# Schematic_khodaparast.net
KiCad netlist of a schematic drawn in Altium Designer
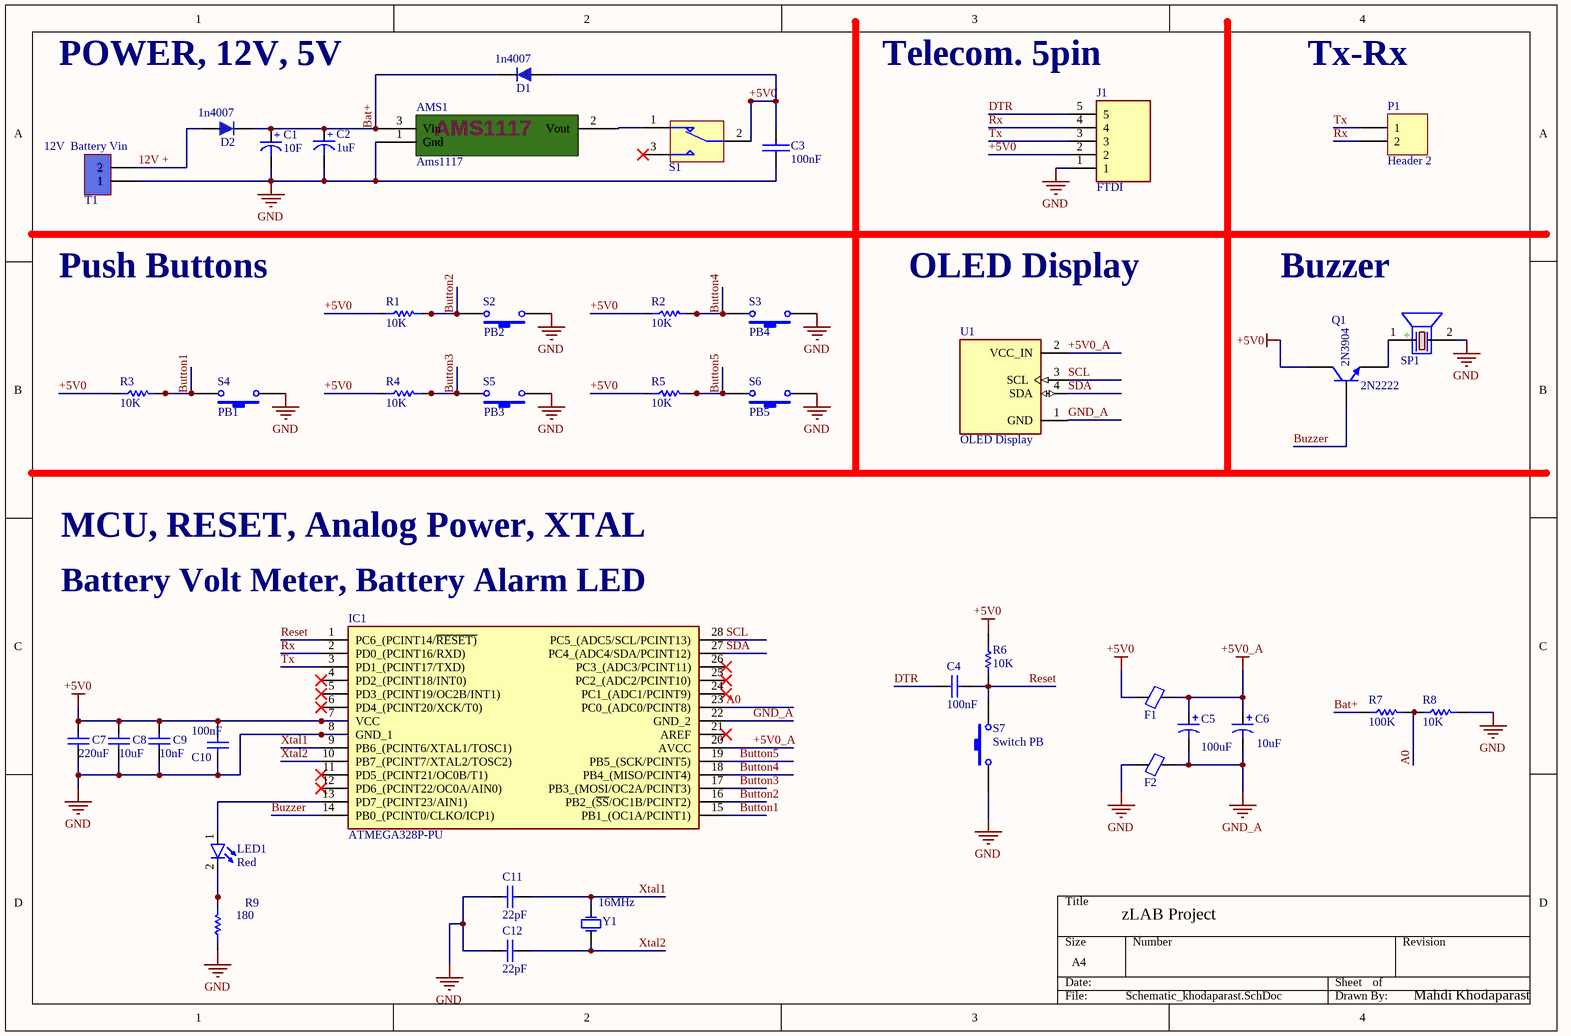
[diagram p0: Schematic_khodaparast.SchDoc]

(export (version "E")
  (design (tool "Eeschema 10.0.6"))
  (components
    (comp (ref "AMS1")
      (value "Ams1117")
      (footprint "Ams1117-3v3")
      (libsource (lib "AMS1117") (part "Ams1117"))
    )
    (comp (ref "C1")
      (value "10F")
      (footprint "Cap1206_(3216X18L)Size A")
      (description "Polar Capacitor")
      (fields (field (name "VOLTAGE") "16V") (field (name "DESIGNER") "Saeid Jorablo"))
      (libsource (lib "full (2)") (part "Cap-Polar"))
    )
    (comp (ref "C2")
      (value "1uF")
      (footprint "Cap1206_(3216X18L)Size A")
      (description "Polar Capacitor")
      (fields (field (name "VOLTAGE") "16V") (field (name "DESIGNER") "Saeid Jorablo"))
      (libsource (lib "full (2)") (part "Cap-Polar"))
    )
    (comp (ref "C3")
      (value "100nF")
      (footprint "CAP805")
      (description "Bipolar Capacitor")
      (fields (field (name "VOLTAGE") "100V") (field (name "DESIGNER") "Saeid Jorablo"))
      (libsource (lib "full (2)") (part "Cap-Bipolar"))
    )
    (comp (ref "C4")
      (value "100nF")
      (footprint "CAP805")
      (description "CAP 0805")
      (fields (field (name "DESIGNER") "Abbas Basereh"))
      (libsource (lib "Altium") (part "CAP SMD 0805"))
    )
    (comp (ref "C5")
      (value "100uF")
      (footprint "Cap1206_(3216X18L)Size A")
      (description "Polarized Capacitor (Radial)")
      (fields (field (name "Comment") "Cap Pol1") (field (name "PUBLISHER") "Altium Limited"))
      (libsource (lib "Miscellaneous Devices") (part "Cap Pol1"))
    )
    (comp (ref "C6")
      (value "10uF")
      (footprint "Cap1206_(3216X18L)Size A")
      (description "Polarized Capacitor (Radial)")
      (fields (field (name "Comment") "Cap Pol1") (field (name "PUBLISHER") "Altium Limited"))
      (libsource (lib "Miscellaneous Devices") (part "Cap Pol1"))
    )
    (comp (ref "C7")
      (value "220uF")
      (footprint "CAP805")
      (description "Capacitor")
      (fields (field (name "Comment") "Cap") (field (name "PUBLISHER") "Altium Limited"))
      (libsource (lib "Miscellaneous Devices") (part "Cap"))
    )
    (comp (ref "C8")
      (value "10uF")
      (footprint "CAP805")
      (description "Capacitor")
      (fields (field (name "Comment") "Cap") (field (name "PUBLISHER") "Altium Limited"))
      (libsource (lib "Miscellaneous Devices") (part "Cap"))
    )
    (comp (ref "C9")
      (value "10nF")
      (footprint "CAP805")
      (description "Capacitor")
      (fields (field (name "Comment") "Cap") (field (name "PUBLISHER") "Altium Limited"))
      (libsource (lib "Miscellaneous Devices") (part "Cap"))
    )
    (comp (ref "C10")
      (value "100nF")
      (footprint "CAP805")
      (description "CAP 0805")
      (fields (field (name "DESIGNER") "Abbas Basereh"))
      (libsource (lib "Altium") (part "CAP SMD 0805"))
    )
    (comp (ref "C11")
      (value "22pF")
      (footprint "CAP805")
      (description "CAP 0805")
      (fields (field (name "DESIGNER") "Abbas Basereh"))
      (libsource (lib "Altium") (part "CAP SMD 0805"))
    )
    (comp (ref "C12")
      (value "22pF")
      (footprint "CAP805")
      (description "CAP 0805")
      (fields (field (name "DESIGNER") "Abbas Basereh"))
      (libsource (lib "Altium") (part "CAP SMD 0805"))
    )
    (comp (ref "D1")
      (value "1n4007")
      (footprint "DIOM4629X24N")
      (description "Standard Rectifiers")
      (fields (field (name "MANUFACTURER") "DC COMPONENTS") (field (name "DESIGNER") "Abbas Basereh"))
      (libsource (lib "Altium") (part "1n4007 SMD M7"))
    )
    (comp (ref "D2")
      (value "1n4007")
      (footprint "DIOM4629X24N")
      (description "Standard Rectifiers")
      (fields (field (name "MANUFACTURER") "DC COMPONENTS") (field (name "DESIGNER") "Abbas Basereh"))
      (libsource (lib "Altium") (part "1n4007 SMD M7"))
    )
    (comp (ref "F1")
      (value "Ferrite Bead SMD")
      (footprint "FB0805")
      (fields (field (name "DESIGNER") "Ali Hafizi"))
      (libsource (lib "Altium") (part "Ferrite Bead SMD Package"))
    )
    (comp (ref "F2")
      (value "Ferrite Bead SMD")
      (footprint "FB0805")
      (fields (field (name "DESIGNER") "Ali Hafizi"))
      (libsource (lib "Altium") (part "Ferrite Bead SMD Package"))
    )
    (comp (ref "IC1")
      (value "ATMEGA328P-PU")
      (footprint "27_DIP_7.62mm")
      (description "Integrated Circuit")
      (fields (field (name "MOUSER PART NUMBER") "556-ATMEGA328P-PU"))
      (libsource (lib "SamacSys") (part "ATMEGA328P-PU"))
    )
    (comp (ref "J1")
      (value "FTDI")
      (footprint "HDR1X5")
      (description "Connector")
      (fields
        (field (name "MANUFACTURER_PART_NUMBER") "171813-0005")
        (field (name "MOUSER PART NUMBER") "538-171813-0005")
      )
      (libsource (lib "*") (part "171813-0005"))
    )
    (comp (ref "LED1")
      (value "Red")
      (footprint "LED-RED")
      (description "LED")
      (fields (field (name "COLOR") "Red") (field (name "DESIGNER") "Saeid Jorablo"))
      (libsource (lib "full (2)") (part "LED"))
    )
    (comp (ref "P1")
      (value "Header 2")
      (footprint "HDR1X2")
      (description "Header, 2-Pin")
      (fields (field (name "PUBLISHER") "Altium Limited"))
      (libsource (lib "Altium") (part "Header 2"))
    )
    (comp (ref "Q1")
      (value "2N2222")
      (footprint "2N3904")
      (description "NPN Transistor")
      (libsource (lib "Altium") (part "2N3904"))
    )
    (comp (ref "R1")
      (value "10K")
      (footprint "RES 0805 (2012X06L)")
      (description "Resistor")
      (fields (field (name "TOLERANCE") "5%") (field (name "POWER") "1/8 W"))
      (libsource (lib "full (2)") (part "Resistor"))
    )
    (comp (ref "R2")
      (value "10K")
      (footprint "RES 0805 (2012X06L)")
      (description "Resistor")
      (fields (field (name "TOLERANCE") "5%") (field (name "POWER") "1/8 W"))
      (libsource (lib "full (2)") (part "Resistor"))
    )
    (comp (ref "R3")
      (value "10K")
      (footprint "RES 0805 (2012X06L)")
      (description "Resistor")
      (fields (field (name "TOLERANCE") "5%") (field (name "POWER") "1/8 W"))
      (libsource (lib "full (2)") (part "Resistor"))
    )
    (comp (ref "R4")
      (value "10K")
      (footprint "RES 0805 (2012X06L)")
      (description "Resistor")
      (fields (field (name "TOLERANCE") "5%") (field (name "POWER") "1/8 W"))
      (libsource (lib "full (2)") (part "Resistor"))
    )
    (comp (ref "R5")
      (value "10K")
      (footprint "RES 0805 (2012X06L)")
      (description "Resistor")
      (fields (field (name "TOLERANCE") "5%") (field (name "POWER") "1/8 W"))
      (libsource (lib "full (2)") (part "Resistor"))
    )
    (comp (ref "R6")
      (value "10K")
      (footprint "RES 0805 (2012X06L)")
      (description "Resistor")
      (fields (field (name "Comment") "Res1") (field (name "PUBLISHER") "Altium Limited"))
      (libsource (lib "Miscellaneous Devices") (part "Res1"))
    )
    (comp (ref "R7")
      (value "100K")
      (footprint "RES 0805 (2012X06L)")
      (description "Resistor")
      (fields (field (name "TOLERANCE") "5%") (field (name "POWER") "1/8 W"))
      (libsource (lib "full (2)") (part "Resistor"))
    )
    (comp (ref "R8")
      (value "10K")
      (footprint "RES 0805 (2012X06L)")
      (description "Resistor")
      (fields (field (name "TOLERANCE") "5%") (field (name "POWER") "1/8 W"))
      (libsource (lib "full (2)") (part "Resistor"))
    )
    (comp (ref "R9")
      (value "180")
      (footprint "RES 0805 (2012X06L)")
      (description "Resistor")
      (fields (field (name "TOLERANCE") "5%") (field (name "POWER") "1/8 W"))
      (libsource (lib "full (2)") (part "Resistor"))
    )
    (comp (ref "S1")
      (value "Switch SPDT_Subminiator")
      (footprint "SPDT Subminiator")
      (description "Subminiator SPDT Switch")
      (libsource (lib "full (2)") (part "Switch SPDT_Subminiator"))
    )
    (comp (ref "S2")
      (value "PB2")
      (footprint "SW-PB")
      (description "Push Button Switch")
      (libsource (lib "full (2)") (part "Switch PB"))
    )
    (comp (ref "S3")
      (value "PB4")
      (footprint "SW-PB")
      (description "Push Button Switch")
      (libsource (lib "full (2)") (part "Switch PB"))
    )
    (comp (ref "S4")
      (value "PB1")
      (footprint "SW-PB")
      (description "Push Button Switch")
      (libsource (lib "full (2)") (part "Switch PB"))
    )
    (comp (ref "S5")
      (value "PB3")
      (footprint "SW-PB")
      (description "Push Button Switch")
      (libsource (lib "full (2)") (part "Switch PB"))
    )
    (comp (ref "S6")
      (value "PB5")
      (footprint "SW-PB")
      (description "Push Button Switch")
      (libsource (lib "full (2)") (part "Switch PB"))
    )
    (comp (ref "S7")
      (value "Switch PB")
      (footprint "SW-PB")
      (description "Push Button Switch")
      (libsource (lib "full (2)") (part "Switch PB"))
    )
    (comp (ref "SP1")
      (value "~")
      (footprint "BUZZER 7.62mm DC")
      (description "PIEZO BUZZER ACTIVE")
      (fields (field (name "DESIGNER") "Abbas Basereh") (field (name "PUBLISHER") "Abbas Basereh"))
      (libsource (lib "Altium") (part "PIEZO BUZZER"))
    )
    (comp (ref "T1")
      (value "12V  Battery Vin")
      (footprint "KF301 2PIN")
      (description "Terminal 2 Pin 250VAC 16A")
      (fields (field (name "DESIGNER") "Abbas Basereh"))
      (libsource (lib "Altium") (part "KF301-2Pin_Terminal"))
    )
    (comp (ref "U1")
      (value "OLED Display")
      (footprint "MODULE_DM-OLED096-636")
      (description "0.96â€ 128 X 64 MONOCHROME GRAPHIC OLED DISPLAY MODULE - I2C")
      (fields (field (name "MF") "Display Module") (field (name "MP") "DM-OLED096-636"))
      (libsource (lib "DM-OLED096-636") (part "DM-OLED096-636"))
    )
    (comp (ref "Y1")
      (value "16MHz")
      (footprint "XTAL 16MHZ")
      (description "XTAL Crystal")
      (fields (field (name "DESIGNER") "ABBAS BASEREH"))
      (libsource (lib "Altium") (part "XTAL"))
    )
  )
  (nets
    (net (code "1") (name "+5V0") (class "Default")
      (node (ref "C10") (pin "1") (pinfunction "1_1") (pintype "passive"))
      (node (ref "C3") (pin "1") (pinfunction "+_1") (pintype "passive"))
      (node (ref "C7") (pin "2") (pinfunction "2_2") (pintype "passive"))
      (node (ref "C8") (pin "2") (pinfunction "2_2") (pintype "passive"))
      (node (ref "C9") (pin "2") (pinfunction "2_2") (pintype "passive"))
      (node (ref "D1") (pin "1") (pintype "passive"))
      (node (ref "F1") (pin "1") (pinfunction "1_1") (pintype "passive"))
      (node (ref "IC1") (pin "7") (pinfunction "VCC_7") (pintype "passive"))
      (node (ref "J1") (pin "2") (pinfunction "2_2") (pintype "passive"))
      (node (ref "Q1") (pin "3") (pinfunction "C_3") (pintype "passive"))
      (node (ref "R1") (pin "1") (pinfunction "1_1") (pintype "passive"))
      (node (ref "R2") (pin "1") (pinfunction "1_1") (pintype "passive"))
      (node (ref "R3") (pin "1") (pinfunction "1_1") (pintype "passive"))
      (node (ref "R4") (pin "1") (pinfunction "1_1") (pintype "passive"))
      (node (ref "R5") (pin "1") (pinfunction "1_1") (pintype "passive"))
      (node (ref "R6") (pin "2") (pinfunction "2_2") (pintype "passive"))
      (node (ref "S1") (pin "2") (pinfunction "2_2") (pintype "passive"))
    )
    (net (code "2") (name "+5V0_A") (class "Default")
      (node (ref "C5") (pin "1") (pinfunction "1_1") (pintype "passive"))
      (node (ref "C6") (pin "1") (pinfunction "1_1") (pintype "passive"))
      (node (ref "F1") (pin "2") (pinfunction "2_2") (pintype "passive"))
      (node (ref "IC1") (pin "20") (pinfunction "AVCC_20") (pintype "passive"))
      (node (ref "U1") (pin "2") (pinfunction "VCC_IN_2") (pintype "power_in"))
    )
    (net (code "3") (name "/12V +") (class "Default")
      (node (ref "D2") (pin "1") (pintype "passive"))
      (node (ref "T1") (pin "2") (pinfunction "2_2") (pintype "passive"))
    )
    (net (code "4") (name "/A0") (class "Default")
      (node (ref "IC1") (pin "23") (pinfunction "PC0_(ADC0/PCINT8)_23") (pintype "passive"))
      (node (ref "R7") (pin "2") (pinfunction "2_2") (pintype "passive"))
      (node (ref "R8") (pin "1") (pinfunction "1_1") (pintype "passive"))
    )
    (net (code "5") (name "/Bat+") (class "Default")
      (node (ref "AMS1") (pin "3") (pinfunction "Vin_3") (pintype "passive"))
      (node (ref "C1") (pin "1") (pinfunction "+_1") (pintype "passive"))
      (node (ref "C2") (pin "1") (pinfunction "+_1") (pintype "passive"))
      (node (ref "D1") (pin "2") (pintype "passive"))
      (node (ref "D2") (pin "2") (pintype "passive"))
      (node (ref "R7") (pin "1") (pinfunction "1_1") (pintype "passive"))
    )
    (net (code "6") (name "/Button1") (class "Default")
      (node (ref "IC1") (pin "15") (pinfunction "PB1_(OC1A/PCINT1)_15") (pintype "passive"))
      (node (ref "R3") (pin "2") (pinfunction "2_2") (pintype "passive"))
      (node (ref "S4") (pin "2") (pinfunction "2_2") (pintype "passive"))
    )
    (net (code "7") (name "/Button2") (class "Default")
      (node (ref "IC1") (pin "16") (pinfunction "PB2_(~{SS}/OC1B/PCINT2)_16") (pintype "passive"))
      (node (ref "R1") (pin "2") (pinfunction "2_2") (pintype "passive"))
      (node (ref "S2") (pin "2") (pinfunction "2_2") (pintype "passive"))
    )
    (net (code "8") (name "/Button3") (class "Default")
      (node (ref "IC1") (pin "17") (pinfunction "PB3_(MOSI/OC2A/PCINT3)_17") (pintype "passive"))
      (node (ref "R4") (pin "2") (pinfunction "2_2") (pintype "passive"))
      (node (ref "S5") (pin "2") (pinfunction "2_2") (pintype "passive"))
    )
    (net (code "9") (name "/Button4") (class "Default")
      (node (ref "IC1") (pin "18") (pinfunction "PB4_(MISO/PCINT4)_18") (pintype "passive"))
      (node (ref "R2") (pin "2") (pinfunction "2_2") (pintype "passive"))
      (node (ref "S3") (pin "2") (pinfunction "2_2") (pintype "passive"))
    )
    (net (code "10") (name "/Button5") (class "Default")
      (node (ref "IC1") (pin "19") (pinfunction "PB5_(SCK/PCINT5)_19") (pintype "passive"))
      (node (ref "R5") (pin "2") (pinfunction "2_2") (pintype "passive"))
      (node (ref "S6") (pin "2") (pinfunction "2_2") (pintype "passive"))
    )
    (net (code "11") (name "/Buzzer") (class "Default")
      (node (ref "IC1") (pin "14") (pinfunction "PB0_(PCINT0/CLKO/ICP1)_14") (pintype "passive"))
      (node (ref "Q1") (pin "2") (pinfunction "B_2") (pintype "passive"))
    )
    (net (code "12") (name "/DTR") (class "Default")
      (node (ref "C4") (pin "2") (pinfunction "2_2") (pintype "passive"))
      (node (ref "J1") (pin "5") (pinfunction "5_5") (pintype "passive"))
    )
    (net (code "13") (name "/Reset") (class "Default")
      (node (ref "C4") (pin "1") (pinfunction "1_1") (pintype "passive"))
      (node (ref "IC1") (pin "1") (pinfunction "PC6_(PCINT14/~{RESET)}_1") (pintype "passive"))
      (node (ref "R6") (pin "1") (pinfunction "1_1") (pintype "passive"))
      (node (ref "S7") (pin "2") (pinfunction "2_2") (pintype "passive"))
    )
    (net (code "14") (name "/Rx") (class "Default")
      (node (ref "IC1") (pin "2") (pinfunction "PD0_(PCINT16/RXD)_2") (pintype "passive"))
      (node (ref "J1") (pin "4") (pinfunction "4_4") (pintype "passive"))
      (node (ref "P1") (pin "2") (pinfunction "2_2") (pintype "passive"))
    )
    (net (code "15") (name "/SCL") (class "Default")
      (node (ref "IC1") (pin "28") (pinfunction "PC5_(ADC5/SCL/PCINT13)_28") (pintype "passive"))
      (node (ref "U1") (pin "3") (pinfunction "SCL_3") (pintype "input"))
    )
    (net (code "16") (name "/SDA") (class "Default")
      (node (ref "IC1") (pin "27") (pinfunction "PC4_(ADC4/SDA/PCINT12)_27") (pintype "passive"))
      (node (ref "U1") (pin "4") (pinfunction "SDA_4") (pintype "bidirectional"))
    )
    (net (code "17") (name "/Tx") (class "Default")
      (node (ref "IC1") (pin "3") (pinfunction "PD1_(PCINT17/TXD)_3") (pintype "passive"))
      (node (ref "J1") (pin "3") (pinfunction "3_3") (pintype "passive"))
      (node (ref "P1") (pin "1") (pinfunction "1_1") (pintype "passive"))
    )
    (net (code "18") (name "/Xtal1") (class "Default")
      (node (ref "C11") (pin "1") (pinfunction "1_1") (pintype "passive"))
      (node (ref "IC1") (pin "9") (pinfunction "PB6_(PCINT6/XTAL1/TOSC1)_9") (pintype "passive"))
      (node (ref "Y1") (pin "2") (pinfunction "OSC2_2") (pintype "passive"))
    )
    (net (code "19") (name "/Xtal2") (class "Default")
      (node (ref "C12") (pin "1") (pinfunction "1_1") (pintype "passive"))
      (node (ref "IC1") (pin "10") (pinfunction "PB7_(PCINT7/XTAL2/TOSC2)_10") (pintype "passive"))
      (node (ref "Y1") (pin "1") (pinfunction "OSC1_1") (pintype "passive"))
    )
    (net (code "20") (name "GND") (class "Default")
      (node (ref "AMS1") (pin "1") (pinfunction "Gnd_1") (pintype "passive"))
      (node (ref "C1") (pin "2") (pinfunction "-_2") (pintype "passive"))
      (node (ref "C10") (pin "2") (pinfunction "2_2") (pintype "passive"))
      (node (ref "C11") (pin "2") (pinfunction "2_2") (pintype "passive"))
      (node (ref "C12") (pin "2") (pinfunction "2_2") (pintype "passive"))
      (node (ref "C2") (pin "2") (pinfunction "-_2") (pintype "passive"))
      (node (ref "C3") (pin "2") (pinfunction "-_2") (pintype "passive"))
      (node (ref "C7") (pin "1") (pinfunction "1_1") (pintype "passive"))
      (node (ref "C8") (pin "1") (pinfunction "1_1") (pintype "passive"))
      (node (ref "C9") (pin "1") (pinfunction "1_1") (pintype "passive"))
      (node (ref "F2") (pin "1") (pinfunction "1_1") (pintype "passive"))
      (node (ref "IC1") (pin "8") (pinfunction "GND_1_8") (pintype "passive"))
      (node (ref "J1") (pin "1") (pinfunction "1_1") (pintype "passive"))
      (node (ref "R8") (pin "2") (pinfunction "2_2") (pintype "passive"))
      (node (ref "R9") (pin "1") (pinfunction "1_1") (pintype "passive"))
      (node (ref "S2") (pin "1") (pinfunction "1_1") (pintype "passive"))
      (node (ref "S3") (pin "1") (pinfunction "1_1") (pintype "passive"))
      (node (ref "S4") (pin "1") (pinfunction "1_1") (pintype "passive"))
      (node (ref "S5") (pin "1") (pinfunction "1_1") (pintype "passive"))
      (node (ref "S6") (pin "1") (pinfunction "1_1") (pintype "passive"))
      (node (ref "S7") (pin "1") (pinfunction "1_1") (pintype "passive"))
      (node (ref "SP1") (pin "2") (pinfunction "-_2") (pintype "passive"))
      (node (ref "T1") (pin "1") (pinfunction "1_1") (pintype "passive"))
    )
    (net (code "21") (name "GND_A") (class "Default")
      (node (ref "C5") (pin "2") (pinfunction "2_2") (pintype "passive"))
      (node (ref "C6") (pin "2") (pinfunction "2_2") (pintype "passive"))
      (node (ref "F2") (pin "2") (pinfunction "2_2") (pintype "passive"))
      (node (ref "IC1") (pin "22") (pinfunction "GND_2_22") (pintype "passive"))
      (node (ref "U1") (pin "1") (pinfunction "GND_1") (pintype "power_in"))
    )
    (net (code "22") (name "Net-(AMS1-Vout)") (class "Default")
      (node (ref "AMS1") (pin "2") (pinfunction "Vout_2") (pintype "passive"))
      (node (ref "S1") (pin "1") (pinfunction "1_1") (pintype "passive"))
    )
    (net (code "23") (name "Net-(IC1-PD7_(PCINT23{slash}AIN1))") (class "Default")
      (node (ref "IC1") (pin "13") (pinfunction "PD7_(PCINT23/AIN1)_13") (pintype "passive"))
      (node (ref "LED1") (pin "1") (pinfunction "A_1") (pintype "passive"))
    )
    (net (code "24") (name "Net-(LED1-K)") (class "Default")
      (node (ref "LED1") (pin "2") (pinfunction "K_2") (pintype "passive"))
      (node (ref "R9") (pin "2") (pinfunction "2_2") (pintype "passive"))
    )
    (net (code "25") (name "Net-(Q1-E)") (class "Default")
      (node (ref "Q1") (pin "1") (pinfunction "E_1") (pintype "passive"))
      (node (ref "SP1") (pin "1") (pinfunction "+_1") (pintype "passive"))
    )
    (net (code "26") (name "unconnected-(IC1-AREF-Pad21)") (class "Default")
      (node (ref "IC1") (pin "21") (pinfunction "AREF_21") (pintype "passive+no_connect"))
    )
    (net (code "27") (name "unconnected-(IC1-PC1_(ADC1{slash}PCINT9)-Pad24)") (class "Default")
      (node (ref "IC1") (pin "24") (pinfunction "PC1_(ADC1/PCINT9)_24") (pintype "passive+no_connect"))
    )
    (net (code "28") (name "unconnected-(IC1-PC2_(ADC2{slash}PCINT10)-Pad25)") (class "Default")
      (node (ref "IC1") (pin "25") (pinfunction "PC2_(ADC2/PCINT10)_25") (pintype "passive+no_connect"))
    )
    (net (code "29") (name "unconnected-(IC1-PC3_(ADC3{slash}PCINT11)-Pad26)") (class "Default")
      (node (ref "IC1") (pin "26") (pinfunction "PC3_(ADC3/PCINT11)_26") (pintype "passive+no_connect"))
    )
    (net (code "30") (name "unconnected-(IC1-PD2_(PCINT18{slash}INT0)-Pad4)") (class "Default")
      (node (ref "IC1") (pin "4") (pinfunction "PD2_(PCINT18/INT0)_4") (pintype "passive+no_connect"))
    )
    (net (code "31") (name "unconnected-(IC1-PD3_(PCINT19{slash}OC2B{slash}INT1)-Pad5)") (class "Default")
      (node (ref "IC1") (pin "5") (pinfunction "PD3_(PCINT19/OC2B/INT1)_5") (pintype "passive+no_connect"))
    )
    (net (code "32") (name "unconnected-(IC1-PD4_(PCINT20{slash}XCK{slash}T0)-Pad6)") (class "Default")
      (node (ref "IC1") (pin "6") (pinfunction "PD4_(PCINT20/XCK/T0)_6") (pintype "passive+no_connect"))
    )
    (net (code "33") (name "unconnected-(IC1-PD5_(PCINT21{slash}OC0B{slash}T1)-Pad11)") (class "Default")
      (node (ref "IC1") (pin "11") (pinfunction "PD5_(PCINT21/OC0B/T1)_11") (pintype "passive+no_connect"))
    )
    (net (code "34") (name "unconnected-(IC1-PD6_(PCINT22{slash}OC0A{slash}AIN0)-Pad12)") (class "Default")
      (node (ref "IC1") (pin "12") (pinfunction "PD6_(PCINT22/OC0A/AIN0)_12") (pintype "passive+no_connect"))
    )
    (net (code "35") (name "unconnected-(S1-Pad3)") (class "Default")
      (node (ref "S1") (pin "3") (pinfunction "3_3") (pintype "passive+no_connect"))
    )
  )
)
